# Lightpack5_5L.net
KiCad netlist of a schematic drawn in EAGLE
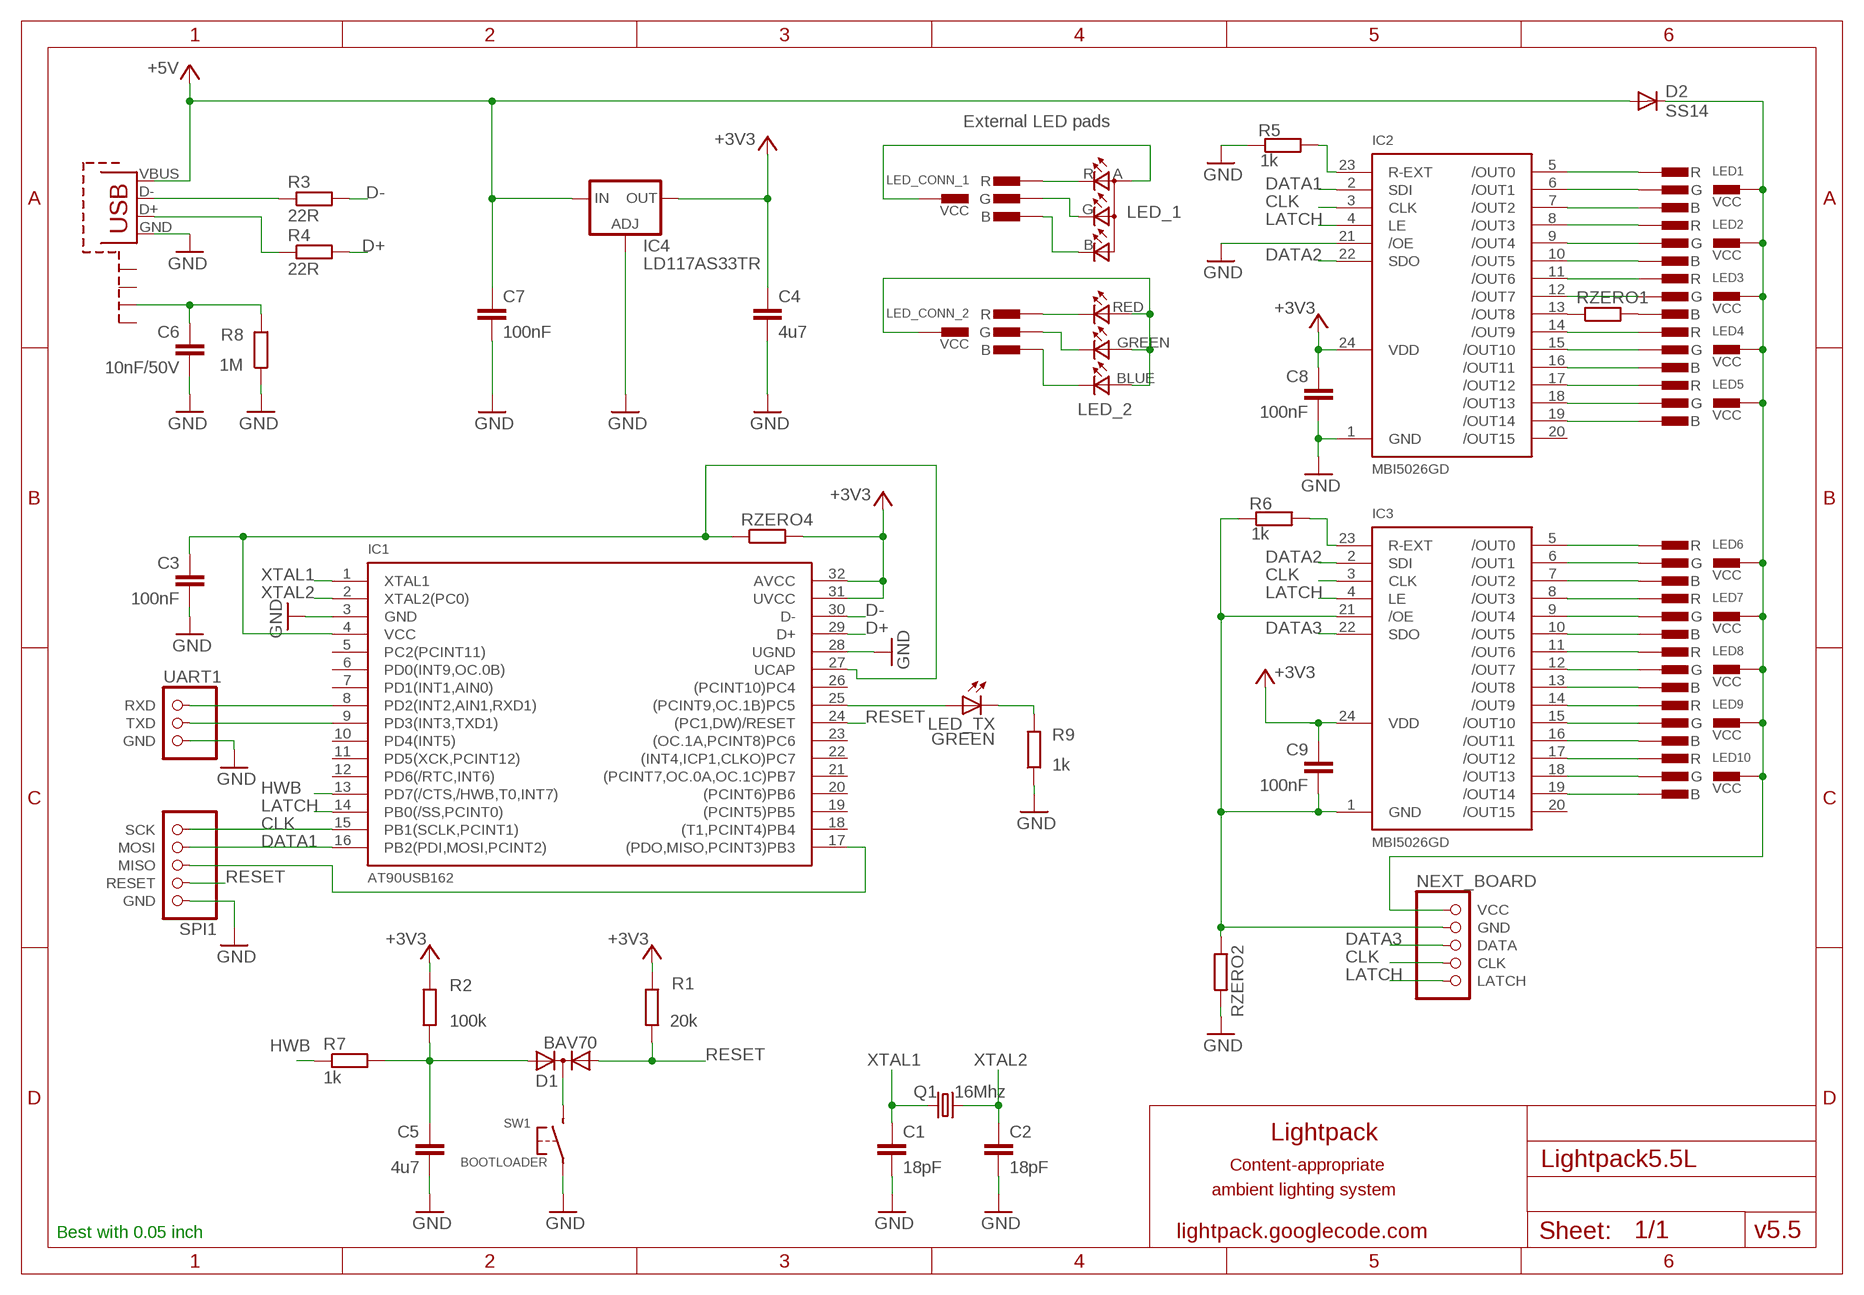
[diagram p0: schematic, sheet 1]

(export (version "E")
  (design (tool "Eeschema 10.0.6"))
  (components
    (comp (ref "C1")
      (value "18pF")
      (footprint "eagle-import:C1206")
      (libsource (lib "eagle-import") (part "C-EUC1206"))
    )
    (comp (ref "C2")
      (value "18pF")
      (footprint "eagle-import:C1206")
      (libsource (lib "eagle-import") (part "C-EUC1206"))
    )
    (comp (ref "C3")
      (value "100nF")
      (footprint "eagle-import:C1206")
      (libsource (lib "eagle-import") (part "C-EUC1206"))
    )
    (comp (ref "C4")
      (value "4u7")
      (footprint "eagle-import:C1206")
      (libsource (lib "eagle-import") (part "C-EUC1206"))
    )
    (comp (ref "C5")
      (value "4u7")
      (footprint "eagle-import:C1206")
      (libsource (lib "eagle-import") (part "C-EUC1206"))
    )
    (comp (ref "C6")
      (value "10nF/50V")
      (footprint "eagle-import:C1206")
      (libsource (lib "eagle-import") (part "C-EUC1206"))
    )
    (comp (ref "C7")
      (value "100nF")
      (footprint "eagle-import:C1206")
      (libsource (lib "eagle-import") (part "C-EUC1206"))
    )
    (comp (ref "C8")
      (value "100nF")
      (footprint "eagle-import:C1206")
      (libsource (lib "eagle-import") (part "C-EUC1206"))
    )
    (comp (ref "C9")
      (value "100nF")
      (footprint "eagle-import:C1206")
      (libsource (lib "eagle-import") (part "C-EUC1206"))
    )
    (comp (ref "D1")
      (value "BAV70")
      (footprint "eagle-import:SOT23")
      (libsource (lib "eagle-import") (part "DIODE-2AC|CASOT23"))
    )
    (comp (ref "D2")
      (value "SS14")
      (footprint "eagle-import:SMB")
      (libsource (lib "eagle-import") (part "DIODE-SMB"))
    )
    (comp (ref "IC1")
      (value "AT90USB162")
      (footprint "eagle-import:TQFP32")
      (libsource (lib "eagle-import") (part "AT90USB162"))
    )
    (comp (ref "IC2")
      (value "MBI5026GD")
      (footprint "eagle-import:SOP24-300-1.27")
      (libsource (lib "eagle-import") (part "MBI5026GD"))
    )
    (comp (ref "IC3")
      (value "MBI5026GD")
      (footprint "eagle-import:SOP24-300-1.27")
      (libsource (lib "eagle-import") (part "MBI5026GD"))
    )
    (comp (ref "IC4")
      (value "LD117AS33TR")
      (footprint "eagle-import:SOT223")
      (libsource (lib "eagle-import") (part "LD117A?S33TR"))
    )
    (comp (ref "LED1")
      (value "CON-RGB-LED")
      (footprint "eagle-import:CON-RGB-LED")
      (libsource (lib "eagle-import") (part "CON-RGB-LED"))
    )
    (comp (ref "LED2")
      (value "CON-RGB-LED")
      (footprint "eagle-import:CON-RGB-LED")
      (libsource (lib "eagle-import") (part "CON-RGB-LED"))
    )
    (comp (ref "LED3")
      (value "CON-RGB-LED")
      (footprint "eagle-import:CON-RGB-LED")
      (libsource (lib "eagle-import") (part "CON-RGB-LED"))
    )
    (comp (ref "LED4")
      (value "CON-RGB-LEDVCC-INDENT")
      (footprint "eagle-import:CON-RGB-LED-WITH-VCC-INDENT")
      (libsource (lib "eagle-import") (part "CON-RGB-LEDVCC-INDENT"))
    )
    (comp (ref "LED5")
      (value "CON-RGB-LEDVCC-INDENT")
      (footprint "eagle-import:CON-RGB-LED-WITH-VCC-INDENT")
      (libsource (lib "eagle-import") (part "CON-RGB-LEDVCC-INDENT"))
    )
    (comp (ref "LED6")
      (value "CON-RGB-LED")
      (footprint "eagle-import:CON-RGB-LED")
      (libsource (lib "eagle-import") (part "CON-RGB-LED"))
    )
    (comp (ref "LED7")
      (value "CON-RGB-LED")
      (footprint "eagle-import:CON-RGB-LED")
      (libsource (lib "eagle-import") (part "CON-RGB-LED"))
    )
    (comp (ref "LED8")
      (value "CON-RGB-LED")
      (footprint "eagle-import:CON-RGB-LED")
      (libsource (lib "eagle-import") (part "CON-RGB-LED"))
    )
    (comp (ref "LED9")
      (value "CON-RGB-LED")
      (footprint "eagle-import:CON-RGB-LED")
      (libsource (lib "eagle-import") (part "CON-RGB-LED"))
    )
    (comp (ref "LED10")
      (value "CON-RGB-LED")
      (footprint "eagle-import:CON-RGB-LED")
      (libsource (lib "eagle-import") (part "CON-RGB-LED"))
    )
    (comp (ref "LED_1")
      (value "CLV1A-FKB")
      (footprint "eagle-import:CLV1A-FKB")
      (libsource (lib "eagle-import") (part "CLV1A-FKB"))
    )
    (comp (ref "LED_2")
      (value "TOPLED-3SMD5X5")
      (footprint "eagle-import:SMD-RGB-5X5")
      (libsource (lib "eagle-import") (part "TOPLED-3SMD5X5"))
    )
    (comp (ref "LED_CONN_1")
      (value "CON-RGB-LED")
      (footprint "eagle-import:CON-RGB-LED")
      (libsource (lib "eagle-import") (part "CON-RGB-LED"))
    )
    (comp (ref "LED_CONN_2")
      (value "CON-RGB-LED")
      (footprint "eagle-import:CON-RGB-LED")
      (libsource (lib "eagle-import") (part "CON-RGB-LED"))
    )
    (comp (ref "LED_TX")
      (value "GREEN")
      (footprint "eagle-import:CHIPLED_0805")
      (libsource (lib "eagle-import") (part "LEDCHIPLED_0805"))
    )
    (comp (ref "NEXT_BOARD")
      (value "LED_DRIVER_BOARD")
      (footprint "eagle-import:DATA-CLK-LATCH")
      (libsource (lib "eagle-import") (part "LED_DRIVER_BOARD"))
    )
    (comp (ref "Q1")
      (value "16Mhz")
      (footprint "eagle-import:HC49UP")
      (libsource (lib "eagle-import") (part "CRYSTALHC49UP"))
    )
    (comp (ref "R1")
      (value "20k")
      (footprint "eagle-import:R1206")
      (libsource (lib "eagle-import") (part "R-EU_R1206"))
    )
    (comp (ref "R2")
      (value "100k")
      (footprint "eagle-import:R1206")
      (libsource (lib "eagle-import") (part "R-EU_R1206_2"))
    )
    (comp (ref "R3")
      (value "22R")
      (footprint "eagle-import:R1206")
      (libsource (lib "eagle-import") (part "rcl_R-EU_R1206"))
    )
    (comp (ref "R4")
      (value "22R")
      (footprint "eagle-import:R1206")
      (libsource (lib "eagle-import") (part "rcl_R-EU_R1206"))
    )
    (comp (ref "R5")
      (value "1k")
      (footprint "eagle-import:R1206")
      (libsource (lib "eagle-import") (part "R-EU_R1206"))
    )
    (comp (ref "R6")
      (value "1k")
      (footprint "eagle-import:R1206")
      (libsource (lib "eagle-import") (part "R-EU_R1206"))
    )
    (comp (ref "R7")
      (value "1k")
      (footprint "eagle-import:R1206")
      (libsource (lib "eagle-import") (part "rcl_R-EU_R1206"))
    )
    (comp (ref "R8")
      (value "1M")
      (footprint "eagle-import:R1206")
      (libsource (lib "eagle-import") (part "rcl_R-EU_R1206"))
    )
    (comp (ref "R9")
      (value "1k")
      (footprint "eagle-import:R1206")
      (libsource (lib "eagle-import") (part "rcl_R-EU_R1206"))
    )
    (comp (ref "RZERO1")
      (value "R-EU_R1206_2")
      (footprint "eagle-import:R1206")
      (libsource (lib "eagle-import") (part "R-EU_R1206_2"))
    )
    (comp (ref "RZERO2")
      (value "0")
      (footprint "eagle-import:R1206")
      (libsource (lib "eagle-import") (part "R-EU_R1206_2"))
    )
    (comp (ref "RZERO4")
      (value "R-EU_R1206_2")
      (footprint "eagle-import:R1206")
      (libsource (lib "eagle-import") (part "R-EU_R1206_2"))
    )
    (comp (ref "SPI1")
      (value "SPI_RST_GND_CONN")
      (footprint "eagle-import:SPI_5")
      (libsource (lib "eagle-import") (part "SPI_RST_GND_CONN"))
    )
    (comp (ref "SW1")
      (value "BOOTLOADER")
      (footprint "eagle-import:BUTTON-SMD")
      (libsource (lib "eagle-import") (part "BUTTON"))
    )
    (comp (ref "UART1")
      (value "UART")
      (footprint "eagle-import:UART")
      (libsource (lib "eagle-import") (part "UART"))
    )
    (comp (ref "X1")
      (value "USB-MB-S")
      (footprint "eagle-import:USB-MB-S")
      (libsource (lib "eagle-import") (part "USB-MB-S"))
    )
  )
  (nets
    (net (code "1") (name "+3V3") (class "Default")
      (node (ref "C4") (pin "1") (pinfunction "1_1") (pintype "passive"))
      (node (ref "C8") (pin "1") (pinfunction "1_1") (pintype "passive"))
      (node (ref "C9") (pin "1") (pinfunction "1_1") (pintype "passive"))
      (node (ref "IC1") (pin "31") (pinfunction "UVCC_31") (pintype "bidirectional"))
      (node (ref "IC1") (pin "32") (pinfunction "AVCC_32") (pintype "bidirectional"))
      (node (ref "IC2") (pin "24") (pinfunction "VDD_24") (pintype "bidirectional"))
      (node (ref "IC3") (pin "24") (pinfunction "VDD_24") (pintype "bidirectional"))
      (node (ref "IC4") (pin "4") (pinfunction "OUT_4") (pintype "passive"))
      (node (ref "R1") (pin "2") (pinfunction "2_2") (pintype "passive"))
      (node (ref "R2") (pin "1") (pinfunction "2_1") (pintype "passive"))
      (node (ref "RZERO4") (pin "1") (pinfunction "2_1") (pintype "passive"))
    )
    (net (code "2") (name "+5V") (class "Default")
      (node (ref "C7") (pin "1") (pinfunction "1_1") (pintype "passive"))
      (node (ref "D2") (pin "A") (pinfunction "A_A") (pintype "passive"))
      (node (ref "IC4") (pin "3") (pinfunction "IN_3") (pintype "input"))
      (node (ref "X1") (pin "VBUS") (pinfunction "VBUS_VBUS") (pintype "bidirectional"))
    )
    (net (code "3") (name "/CLK") (class "Default")
      (node (ref "IC1") (pin "15") (pinfunction "PB1(SCLK,PCINT1)_15") (pintype "bidirectional"))
      (node (ref "IC2") (pin "3") (pinfunction "CLK_3") (pintype "bidirectional"))
      (node (ref "IC3") (pin "3") (pinfunction "CLK_3") (pintype "bidirectional"))
      (node (ref "NEXT_BOARD") (pin "CLK") (pinfunction "CLK_CLK") (pintype "passive"))
      (node (ref "SPI1") (pin "SCK") (pinfunction "SCK_SCK") (pintype "passive"))
    )
    (net (code "4") (name "/D+") (class "Default")
      (node (ref "IC1") (pin "29") (pinfunction "D+_29") (pintype "bidirectional"))
      (node (ref "R4") (pin "2") (pinfunction "2_2") (pintype "passive"))
    )
    (net (code "5") (name "/D-") (class "Default")
      (node (ref "IC1") (pin "30") (pinfunction "D-_30") (pintype "bidirectional"))
      (node (ref "R3") (pin "2") (pinfunction "2_2") (pintype "passive"))
    )
    (net (code "6") (name "/DATA1") (class "Default")
      (node (ref "IC1") (pin "16") (pinfunction "PB2(PDI,MOSI,PCINT2)_16") (pintype "bidirectional"))
      (node (ref "IC2") (pin "2") (pinfunction "SDI_2") (pintype "bidirectional"))
      (node (ref "SPI1") (pin "MOSI") (pinfunction "MOSI_MOSI") (pintype "passive"))
    )
    (net (code "7") (name "/DATA2") (class "Default")
      (node (ref "IC2") (pin "22") (pinfunction "SDO_22") (pintype "bidirectional"))
      (node (ref "IC3") (pin "2") (pinfunction "SDI_2") (pintype "bidirectional"))
    )
    (net (code "8") (name "/DATA3") (class "Default")
      (node (ref "IC3") (pin "22") (pinfunction "SDO_22") (pintype "bidirectional"))
      (node (ref "NEXT_BOARD") (pin "DATA") (pinfunction "DATA_DATA") (pintype "passive"))
    )
    (net (code "9") (name "/HWB") (class "Default")
      (node (ref "IC1") (pin "13") (pinfunction "PD7(/CTS,/HWB,T0,INT7)_13") (pintype "bidirectional"))
      (node (ref "R7") (pin "1") (pinfunction "1_1") (pintype "passive"))
    )
    (net (code "10") (name "/LATCH") (class "Default")
      (node (ref "IC1") (pin "14") (pinfunction "PB0(/SS,PCINT0)_14") (pintype "bidirectional"))
      (node (ref "IC2") (pin "4") (pinfunction "LE_4") (pintype "bidirectional"))
      (node (ref "IC3") (pin "4") (pinfunction "LE_4") (pintype "bidirectional"))
      (node (ref "NEXT_BOARD") (pin "LATCH") (pinfunction "LATCH_LATCH") (pintype "passive"))
    )
    (net (code "11") (name "/RESET") (class "Default")
      (node (ref "D1") (pin "1") (pinfunction "A1_1") (pintype "passive"))
      (node (ref "IC1") (pin "24") (pinfunction "(PC1,DW)/RESET_24") (pintype "bidirectional"))
      (node (ref "R1") (pin "1") (pinfunction "1_1") (pintype "passive"))
      (node (ref "SPI1") (pin "RESET") (pinfunction "RESET_RESET") (pintype "passive"))
    )
    (net (code "12") (name "/XTAL1") (class "Default")
      (node (ref "C1") (pin "1") (pinfunction "1_1") (pintype "passive"))
      (node (ref "IC1") (pin "1") (pinfunction "XTAL1_1") (pintype "bidirectional"))
      (node (ref "Q1") (pin "1") (pinfunction "1_1") (pintype "passive"))
    )
    (net (code "13") (name "/XTAL2") (class "Default")
      (node (ref "C2") (pin "1") (pinfunction "1_1") (pintype "passive"))
      (node (ref "IC1") (pin "2") (pinfunction "XTAL2(PC0)_2") (pintype "bidirectional"))
      (node (ref "Q1") (pin "2") (pinfunction "2_2") (pintype "passive"))
    )
    (net (code "14") (name "GND") (class "Default")
      (node (ref "C1") (pin "2") (pinfunction "2_2") (pintype "passive"))
      (node (ref "C2") (pin "2") (pinfunction "2_2") (pintype "passive"))
      (node (ref "C3") (pin "2") (pinfunction "2_2") (pintype "passive"))
      (node (ref "C4") (pin "2") (pinfunction "2_2") (pintype "passive"))
      (node (ref "C5") (pin "2") (pinfunction "2_2") (pintype "passive"))
      (node (ref "C6") (pin "2") (pinfunction "2_2") (pintype "passive"))
      (node (ref "C7") (pin "2") (pinfunction "2_2") (pintype "passive"))
      (node (ref "C8") (pin "2") (pinfunction "2_2") (pintype "passive"))
      (node (ref "IC1") (pin "28") (pinfunction "UGND_28") (pintype "bidirectional"))
      (node (ref "IC1") (pin "3") (pinfunction "GND_3") (pintype "bidirectional"))
      (node (ref "IC2") (pin "1") (pinfunction "GND_1") (pintype "bidirectional"))
      (node (ref "IC2") (pin "21") (pinfunction "/OE_21") (pintype "bidirectional"))
      (node (ref "IC4") (pin "1") (pinfunction "ADJ_1") (pintype "input"))
      (node (ref "R5") (pin "1") (pinfunction "1_1") (pintype "passive"))
      (node (ref "R8") (pin "1") (pinfunction "1_1") (pintype "passive"))
      (node (ref "R9") (pin "1") (pinfunction "1_1") (pintype "passive"))
      (node (ref "RZERO2") (pin "1") (pinfunction "2_1") (pintype "passive"))
      (node (ref "SPI1") (pin "GND") (pinfunction "GND_GND") (pintype "passive"))
      (node (ref "SW1") (pin "1") (pinfunction "1_1") (pintype "passive"))
      (node (ref "UART1") (pin "GND") (pinfunction "GND_GND") (pintype "passive"))
      (node (ref "X1") (pin "GND") (pinfunction "GND_GND") (pintype "bidirectional"))
    )
    (net (code "15") (name "Net-(C6-Pad1)") (class "Default")
      (node (ref "C6") (pin "1") (pinfunction "1_1") (pintype "passive"))
      (node (ref "R8") (pin "2") (pinfunction "2_2") (pintype "passive"))
      (node (ref "X1") (pin "SHIELD3") (pinfunction "SHIELD3_SHIELD3") (pintype "bidirectional"))
    )
    (net (code "16") (name "Net-(D1-A2)") (class "Default")
      (node (ref "C5") (pin "1") (pinfunction "1_1") (pintype "passive"))
      (node (ref "D1") (pin "2") (pinfunction "A2_2") (pintype "passive"))
      (node (ref "R2") (pin "2") (pinfunction "1_2") (pintype "passive"))
      (node (ref "R7") (pin "2") (pinfunction "2_2") (pintype "passive"))
    )
    (net (code "17") (name "Net-(D1-C)") (class "Default")
      (node (ref "D1") (pin "3") (pinfunction "C_3") (pintype "passive"))
      (node (ref "SW1") (pin "2") (pinfunction "2_2") (pintype "passive"))
    )
    (net (code "18") (name "Net-(D2-PadC)") (class "Default")
      (node (ref "D2") (pin "C") (pinfunction "C_C") (pintype "passive"))
      (node (ref "LED1") (pin "VCC") (pinfunction "VCC_VCC") (pintype "bidirectional"))
      (node (ref "LED10") (pin "VCC") (pinfunction "VCC_VCC") (pintype "bidirectional"))
      (node (ref "LED2") (pin "VCC") (pinfunction "VCC_VCC") (pintype "bidirectional"))
      (node (ref "LED3") (pin "VCC") (pinfunction "VCC_VCC") (pintype "bidirectional"))
      (node (ref "LED4") (pin "VCC") (pinfunction "VCC_VCC") (pintype "bidirectional"))
      (node (ref "LED5") (pin "VCC") (pinfunction "VCC_VCC") (pintype "bidirectional"))
      (node (ref "LED6") (pin "VCC") (pinfunction "VCC_VCC") (pintype "bidirectional"))
      (node (ref "LED7") (pin "VCC") (pinfunction "VCC_VCC") (pintype "bidirectional"))
      (node (ref "LED8") (pin "VCC") (pinfunction "VCC_VCC") (pintype "bidirectional"))
      (node (ref "LED9") (pin "VCC") (pinfunction "VCC_VCC") (pintype "bidirectional"))
      (node (ref "NEXT_BOARD") (pin "VCC") (pinfunction "VCC_VCC") (pintype "passive"))
    )
    (net (code "19") (name "Net-(IC1-(PCINT9,OC.1B)PC5)") (class "Default")
      (node (ref "IC1") (pin "25") (pinfunction "(PCINT9,OC.1B)PC5_25") (pintype "bidirectional"))
      (node (ref "LED_TX") (pin "A") (pinfunction "A_A") (pintype "passive"))
    )
    (net (code "20") (name "Net-(IC1-(PDO,MISO,PCINT3)PB3)") (class "Default")
      (node (ref "IC1") (pin "17") (pinfunction "(PDO,MISO,PCINT3)PB3_17") (pintype "bidirectional"))
      (node (ref "SPI1") (pin "MISO") (pinfunction "MISO_MISO") (pintype "passive"))
    )
    (net (code "21") (name "Net-(IC1-PD2(INT2,AIN1,RXD1))") (class "Default")
      (node (ref "IC1") (pin "8") (pinfunction "PD2(INT2,AIN1,RXD1)_8") (pintype "bidirectional"))
      (node (ref "UART1") (pin "RXD") (pinfunction "RXD_RXD") (pintype "passive"))
    )
    (net (code "22") (name "Net-(IC1-PD3(INT3,TXD1))") (class "Default")
      (node (ref "IC1") (pin "9") (pinfunction "PD3(INT3,TXD1)_9") (pintype "bidirectional"))
      (node (ref "UART1") (pin "TXD") (pinfunction "TXD_TXD") (pintype "passive"))
    )
    (net (code "23") (name "Net-(IC1-UCAP)") (class "Default")
      (node (ref "C3") (pin "1") (pinfunction "1_1") (pintype "passive"))
      (node (ref "IC1") (pin "27") (pinfunction "UCAP_27") (pintype "bidirectional"))
      (node (ref "IC1") (pin "4") (pinfunction "VCC_4") (pintype "bidirectional"))
      (node (ref "RZERO4") (pin "2") (pinfunction "1_2") (pintype "passive"))
    )
    (net (code "24") (name "Net-(IC2-R-EXT)") (class "Default")
      (node (ref "IC2") (pin "23") (pinfunction "R-EXT_23") (pintype "bidirectional"))
      (node (ref "R5") (pin "2") (pinfunction "2_2") (pintype "passive"))
    )
    (net (code "25") (name "Net-(IC2-{slash}OUT0)") (class "Default")
      (node (ref "IC2") (pin "5") (pinfunction "/OUT0_5") (pintype "bidirectional"))
      (node (ref "LED1") (pin "R") (pinfunction "R_R") (pintype "bidirectional"))
    )
    (net (code "26") (name "Net-(IC2-{slash}OUT1)") (class "Default")
      (node (ref "IC2") (pin "6") (pinfunction "/OUT1_6") (pintype "bidirectional"))
      (node (ref "LED1") (pin "G") (pinfunction "G_G") (pintype "bidirectional"))
    )
    (net (code "27") (name "Net-(IC2-{slash}OUT2)") (class "Default")
      (node (ref "IC2") (pin "7") (pinfunction "/OUT2_7") (pintype "bidirectional"))
      (node (ref "LED1") (pin "B") (pinfunction "B_B") (pintype "bidirectional"))
    )
    (net (code "28") (name "Net-(IC2-{slash}OUT3)") (class "Default")
      (node (ref "IC2") (pin "8") (pinfunction "/OUT3_8") (pintype "bidirectional"))
      (node (ref "LED2") (pin "R") (pinfunction "R_R") (pintype "bidirectional"))
    )
    (net (code "29") (name "Net-(IC2-{slash}OUT4)") (class "Default")
      (node (ref "IC2") (pin "9") (pinfunction "/OUT4_9") (pintype "bidirectional"))
      (node (ref "LED2") (pin "G") (pinfunction "G_G") (pintype "bidirectional"))
    )
    (net (code "30") (name "Net-(IC2-{slash}OUT5)") (class "Default")
      (node (ref "IC2") (pin "10") (pinfunction "/OUT5_10") (pintype "bidirectional"))
      (node (ref "LED2") (pin "B") (pinfunction "B_B") (pintype "bidirectional"))
    )
    (net (code "31") (name "Net-(IC2-{slash}OUT6)") (class "Default")
      (node (ref "IC2") (pin "11") (pinfunction "/OUT6_11") (pintype "bidirectional"))
      (node (ref "LED3") (pin "R") (pinfunction "R_R") (pintype "bidirectional"))
    )
    (net (code "32") (name "Net-(IC2-{slash}OUT7)") (class "Default")
      (node (ref "IC2") (pin "12") (pinfunction "/OUT7_12") (pintype "bidirectional"))
      (node (ref "LED3") (pin "G") (pinfunction "G_G") (pintype "bidirectional"))
    )
    (net (code "33") (name "Net-(IC2-{slash}OUT8)") (class "Default")
      (node (ref "IC2") (pin "13") (pinfunction "/OUT8_13") (pintype "bidirectional"))
      (node (ref "RZERO1") (pin "2") (pinfunction "1_2") (pintype "passive"))
    )
    (net (code "34") (name "Net-(IC2-{slash}OUT9)") (class "Default")
      (node (ref "IC2") (pin "14") (pinfunction "/OUT9_14") (pintype "bidirectional"))
      (node (ref "LED4") (pin "R") (pinfunction "R_R") (pintype "bidirectional"))
    )
    (net (code "35") (name "Net-(IC2-{slash}OUT10)") (class "Default")
      (node (ref "IC2") (pin "15") (pinfunction "/OUT10_15") (pintype "bidirectional"))
      (node (ref "LED4") (pin "G") (pinfunction "G_G") (pintype "bidirectional"))
    )
    (net (code "36") (name "Net-(IC2-{slash}OUT11)") (class "Default")
      (node (ref "IC2") (pin "16") (pinfunction "/OUT11_16") (pintype "bidirectional"))
      (node (ref "LED4") (pin "B") (pinfunction "B_B") (pintype "bidirectional"))
    )
    (net (code "37") (name "Net-(IC2-{slash}OUT12)") (class "Default")
      (node (ref "IC2") (pin "17") (pinfunction "/OUT12_17") (pintype "bidirectional"))
      (node (ref "LED5") (pin "R") (pinfunction "R_R") (pintype "bidirectional"))
    )
    (net (code "38") (name "Net-(IC2-{slash}OUT13)") (class "Default")
      (node (ref "IC2") (pin "18") (pinfunction "/OUT13_18") (pintype "bidirectional"))
      (node (ref "LED5") (pin "G") (pinfunction "G_G") (pintype "bidirectional"))
    )
    (net (code "39") (name "Net-(IC2-{slash}OUT14)") (class "Default")
      (node (ref "IC2") (pin "19") (pinfunction "/OUT14_19") (pintype "bidirectional"))
      (node (ref "LED5") (pin "B") (pinfunction "B_B") (pintype "bidirectional"))
    )
    (net (code "40") (name "Net-(IC3-GND)") (class "Default")
      (node (ref "C9") (pin "2") (pinfunction "2_2") (pintype "passive"))
      (node (ref "IC3") (pin "1") (pinfunction "GND_1") (pintype "bidirectional"))
      (node (ref "IC3") (pin "21") (pinfunction "/OE_21") (pintype "bidirectional"))
      (node (ref "NEXT_BOARD") (pin "GND") (pinfunction "GND_GND") (pintype "passive"))
      (node (ref "R6") (pin "1") (pinfunction "1_1") (pintype "passive"))
      (node (ref "RZERO2") (pin "2") (pinfunction "1_2") (pintype "passive"))
    )
    (net (code "41") (name "Net-(IC3-R-EXT)") (class "Default")
      (node (ref "IC3") (pin "23") (pinfunction "R-EXT_23") (pintype "bidirectional"))
      (node (ref "R6") (pin "2") (pinfunction "2_2") (pintype "passive"))
    )
    (net (code "42") (name "Net-(IC3-{slash}OUT0)") (class "Default")
      (node (ref "IC3") (pin "5") (pinfunction "/OUT0_5") (pintype "bidirectional"))
      (node (ref "LED6") (pin "R") (pinfunction "R_R") (pintype "bidirectional"))
    )
    (net (code "43") (name "Net-(IC3-{slash}OUT1)") (class "Default")
      (node (ref "IC3") (pin "6") (pinfunction "/OUT1_6") (pintype "bidirectional"))
      (node (ref "LED6") (pin "G") (pinfunction "G_G") (pintype "bidirectional"))
    )
    (net (code "44") (name "Net-(IC3-{slash}OUT2)") (class "Default")
      (node (ref "IC3") (pin "7") (pinfunction "/OUT2_7") (pintype "bidirectional"))
      (node (ref "LED6") (pin "B") (pinfunction "B_B") (pintype "bidirectional"))
    )
    (net (code "45") (name "Net-(IC3-{slash}OUT3)") (class "Default")
      (node (ref "IC3") (pin "8") (pinfunction "/OUT3_8") (pintype "bidirectional"))
      (node (ref "LED7") (pin "R") (pinfunction "R_R") (pintype "bidirectional"))
    )
    (net (code "46") (name "Net-(IC3-{slash}OUT4)") (class "Default")
      (node (ref "IC3") (pin "9") (pinfunction "/OUT4_9") (pintype "bidirectional"))
      (node (ref "LED7") (pin "G") (pinfunction "G_G") (pintype "bidirectional"))
    )
    (net (code "47") (name "Net-(IC3-{slash}OUT5)") (class "Default")
      (node (ref "IC3") (pin "10") (pinfunction "/OUT5_10") (pintype "bidirectional"))
      (node (ref "LED7") (pin "B") (pinfunction "B_B") (pintype "bidirectional"))
    )
    (net (code "48") (name "Net-(IC3-{slash}OUT6)") (class "Default")
      (node (ref "IC3") (pin "11") (pinfunction "/OUT6_11") (pintype "bidirectional"))
      (node (ref "LED8") (pin "R") (pinfunction "R_R") (pintype "bidirectional"))
    )
    (net (code "49") (name "Net-(IC3-{slash}OUT7)") (class "Default")
      (node (ref "IC3") (pin "12") (pinfunction "/OUT7_12") (pintype "bidirectional"))
      (node (ref "LED8") (pin "G") (pinfunction "G_G") (pintype "bidirectional"))
    )
    (net (code "50") (name "Net-(IC3-{slash}OUT8)") (class "Default")
      (node (ref "IC3") (pin "13") (pinfunction "/OUT8_13") (pintype "bidirectional"))
      (node (ref "LED8") (pin "B") (pinfunction "B_B") (pintype "bidirectional"))
    )
    (net (code "51") (name "Net-(IC3-{slash}OUT9)") (class "Default")
      (node (ref "IC3") (pin "14") (pinfunction "/OUT9_14") (pintype "bidirectional"))
      (node (ref "LED9") (pin "R") (pinfunction "R_R") (pintype "bidirectional"))
    )
    (net (code "52") (name "Net-(IC3-{slash}OUT10)") (class "Default")
      (node (ref "IC3") (pin "15") (pinfunction "/OUT10_15") (pintype "bidirectional"))
      (node (ref "LED9") (pin "G") (pinfunction "G_G") (pintype "bidirectional"))
    )
    (net (code "53") (name "Net-(IC3-{slash}OUT11)") (class "Default")
      (node (ref "IC3") (pin "16") (pinfunction "/OUT11_16") (pintype "bidirectional"))
      (node (ref "LED9") (pin "B") (pinfunction "B_B") (pintype "bidirectional"))
    )
    (net (code "54") (name "Net-(IC3-{slash}OUT12)") (class "Default")
      (node (ref "IC3") (pin "17") (pinfunction "/OUT12_17") (pintype "bidirectional"))
      (node (ref "LED10") (pin "R") (pinfunction "R_R") (pintype "bidirectional"))
    )
    (net (code "55") (name "Net-(IC3-{slash}OUT13)") (class "Default")
      (node (ref "IC3") (pin "18") (pinfunction "/OUT13_18") (pintype "bidirectional"))
      (node (ref "LED10") (pin "G") (pinfunction "G_G") (pintype "bidirectional"))
    )
    (net (code "56") (name "Net-(IC3-{slash}OUT14)") (class "Default")
      (node (ref "IC3") (pin "19") (pinfunction "/OUT14_19") (pintype "bidirectional"))
      (node (ref "LED10") (pin "B") (pinfunction "B_B") (pintype "bidirectional"))
    )
    (net (code "57") (name "Net-(LED_1-ANODE)") (class "Default")
      (node (ref "LED_1") (pin "A") (pinfunction "ANODE_A") (pintype "passive"))
      (node (ref "LED_CONN_1") (pin "VCC") (pinfunction "VCC_VCC") (pintype "bidirectional"))
    )
    (net (code "58") (name "Net-(LED_1-CBLUE)") (class "Default")
      (node (ref "LED_1") (pin "B") (pinfunction "CBLUE_B") (pintype "passive"))
      (node (ref "LED_CONN_1") (pin "B") (pinfunction "B_B") (pintype "bidirectional"))
    )
    (net (code "59") (name "Net-(LED_1-CGREEN)") (class "Default")
      (node (ref "LED_1") (pin "G") (pinfunction "CGREEN_G") (pintype "passive"))
      (node (ref "LED_CONN_1") (pin "G") (pinfunction "G_G") (pintype "bidirectional"))
    )
    (net (code "60") (name "Net-(LED_1-CRED)") (class "Default")
      (node (ref "LED_1") (pin "R") (pinfunction "CRED_R") (pintype "passive"))
      (node (ref "LED_CONN_1") (pin "R") (pinfunction "R_R") (pintype "bidirectional"))
    )
    (net (code "61") (name "Net-(LED_2-PadBLUE)") (class "Default")
      (node (ref "LED_2") (pin "BLUE") (pinfunction "BLUE_BLUE") (pintype "passive"))
      (node (ref "LED_2") (pin "GREEN") (pinfunction "GREEN_GREEN") (pintype "passive"))
      (node (ref "LED_2") (pin "RED") (pinfunction "RED_RED") (pintype "passive"))
      (node (ref "LED_CONN_2") (pin "VCC") (pinfunction "VCC_VCC") (pintype "bidirectional"))
    )
    (net (code "62") (name "Net-(LED_2-PadCBLUE)") (class "Default")
      (node (ref "LED_2") (pin "CBLUE") (pinfunction "CBLUE_CBLUE") (pintype "passive"))
      (node (ref "LED_CONN_2") (pin "B") (pinfunction "B_B") (pintype "bidirectional"))
    )
    (net (code "63") (name "Net-(LED_2-PadCGREEN)") (class "Default")
      (node (ref "LED_2") (pin "CGREEN") (pinfunction "CGREEN_CGREEN") (pintype "passive"))
      (node (ref "LED_CONN_2") (pin "G") (pinfunction "G_G") (pintype "bidirectional"))
    )
    (net (code "64") (name "Net-(LED_2-PadCRED)") (class "Default")
      (node (ref "LED_2") (pin "CRED") (pinfunction "CRED_CRED") (pintype "passive"))
      (node (ref "LED_CONN_2") (pin "R") (pinfunction "R_R") (pintype "bidirectional"))
    )
    (net (code "65") (name "Net-(LED_TX-PadC)") (class "Default")
      (node (ref "LED_TX") (pin "C") (pinfunction "C_C") (pintype "passive"))
      (node (ref "R9") (pin "2") (pinfunction "2_2") (pintype "passive"))
    )
    (net (code "66") (name "Net-(R3-Pad1)") (class "Default")
      (node (ref "R3") (pin "1") (pinfunction "1_1") (pintype "passive"))
      (node (ref "X1") (pin "D-") (pinfunction "D-_D-") (pintype "bidirectional"))
    )
    (net (code "67") (name "Net-(R4-Pad1)") (class "Default")
      (node (ref "R4") (pin "1") (pinfunction "1_1") (pintype "passive"))
      (node (ref "X1") (pin "D+") (pinfunction "D+_D+") (pintype "bidirectional"))
    )
    (net (code "68") (name "Net-(RZERO1-2)") (class "Default")
      (node (ref "LED3") (pin "B") (pinfunction "B_B") (pintype "bidirectional"))
      (node (ref "RZERO1") (pin "1") (pinfunction "2_1") (pintype "passive"))
    )
    (net (code "69") (name "unconnected-(IC1-(INT4,ICP1,CLKO)PC7-Pad22)") (class "Default")
      (node (ref "IC1") (pin "22") (pinfunction "(INT4,ICP1,CLKO)PC7_22") (pintype "bidirectional"))
    )
    (net (code "70") (name "unconnected-(IC1-(OC.1A,PCINT8)PC6-Pad23)") (class "Default")
      (node (ref "IC1") (pin "23") (pinfunction "(OC.1A,PCINT8)PC6_23") (pintype "bidirectional"))
    )
    (net (code "71") (name "unconnected-(IC1-(PCINT5)PB5-Pad19)") (class "Default")
      (node (ref "IC1") (pin "19") (pinfunction "(PCINT5)PB5_19") (pintype "bidirectional"))
    )
    (net (code "72") (name "unconnected-(IC1-(PCINT6)PB6-Pad20)") (class "Default")
      (node (ref "IC1") (pin "20") (pinfunction "(PCINT6)PB6_20") (pintype "bidirectional"))
    )
    (net (code "73") (name "unconnected-(IC1-(PCINT7,OC.0A,OC.1C)PB7-Pad21)") (class "Default")
      (node (ref "IC1") (pin "21") (pinfunction "(PCINT7,OC.0A,OC.1C)PB7_21") (pintype "bidirectional"))
    )
    (net (code "74") (name "unconnected-(IC1-(PCINT10)PC4-Pad26)") (class "Default")
      (node (ref "IC1") (pin "26") (pinfunction "(PCINT10)PC4_26") (pintype "bidirectional"))
    )
    (net (code "75") (name "unconnected-(IC1-(T1,PCINT4)PB4-Pad18)") (class "Default")
      (node (ref "IC1") (pin "18") (pinfunction "(T1,PCINT4)PB4_18") (pintype "bidirectional"))
    )
    (net (code "76") (name "unconnected-(IC1-PC2(PCINT11)-Pad5)") (class "Default")
      (node (ref "IC1") (pin "5") (pinfunction "PC2(PCINT11)_5") (pintype "bidirectional"))
    )
    (net (code "77") (name "unconnected-(IC1-PD0(INT9,OC.0B)-Pad6)") (class "Default")
      (node (ref "IC1") (pin "6") (pinfunction "PD0(INT9,OC.0B)_6") (pintype "bidirectional"))
    )
    (net (code "78") (name "unconnected-(IC1-PD1(INT1,AIN0)-Pad7)") (class "Default")
      (node (ref "IC1") (pin "7") (pinfunction "PD1(INT1,AIN0)_7") (pintype "bidirectional"))
    )
    (net (code "79") (name "unconnected-(IC1-PD4(INT5)-Pad10)") (class "Default")
      (node (ref "IC1") (pin "10") (pinfunction "PD4(INT5)_10") (pintype "bidirectional"))
    )
    (net (code "80") (name "unconnected-(IC1-PD5(XCK,PCINT12)-Pad11)") (class "Default")
      (node (ref "IC1") (pin "11") (pinfunction "PD5(XCK,PCINT12)_11") (pintype "bidirectional"))
    )
    (net (code "81") (name "unconnected-(IC1-PD6({slash}RTC,INT6)-Pad12)") (class "Default")
      (node (ref "IC1") (pin "12") (pinfunction "PD6(/RTC,INT6)_12") (pintype "bidirectional"))
    )
    (net (code "82") (name "unconnected-(IC2-{slash}OUT15-Pad20)") (class "Default")
      (node (ref "IC2") (pin "20") (pinfunction "/OUT15_20") (pintype "bidirectional"))
    )
    (net (code "83") (name "unconnected-(IC3-{slash}OUT15-Pad20)") (class "Default")
      (node (ref "IC3") (pin "20") (pinfunction "/OUT15_20") (pintype "bidirectional"))
    )
    (net (code "84") (name "unconnected-(X1-PadSHIELD1)") (class "Default")
      (node (ref "X1") (pin "SHIELD1") (pinfunction "SHIELD1_SHIELD1") (pintype "bidirectional"))
    )
    (net (code "85") (name "unconnected-(X1-PadSHIELD2)") (class "Default")
      (node (ref "X1") (pin "SHIELD2") (pinfunction "SHIELD2_SHIELD2") (pintype "bidirectional"))
    )
    (net (code "86") (name "unconnected-(X1-PadSHIELD4)") (class "Default")
      (node (ref "X1") (pin "SHIELD4") (pinfunction "SHIELD4_SHIELD4") (pintype "bidirectional"))
    )
  )
)
